# LIN_break2.net
KiCad netlist of a schematic drawn in Altium Designer
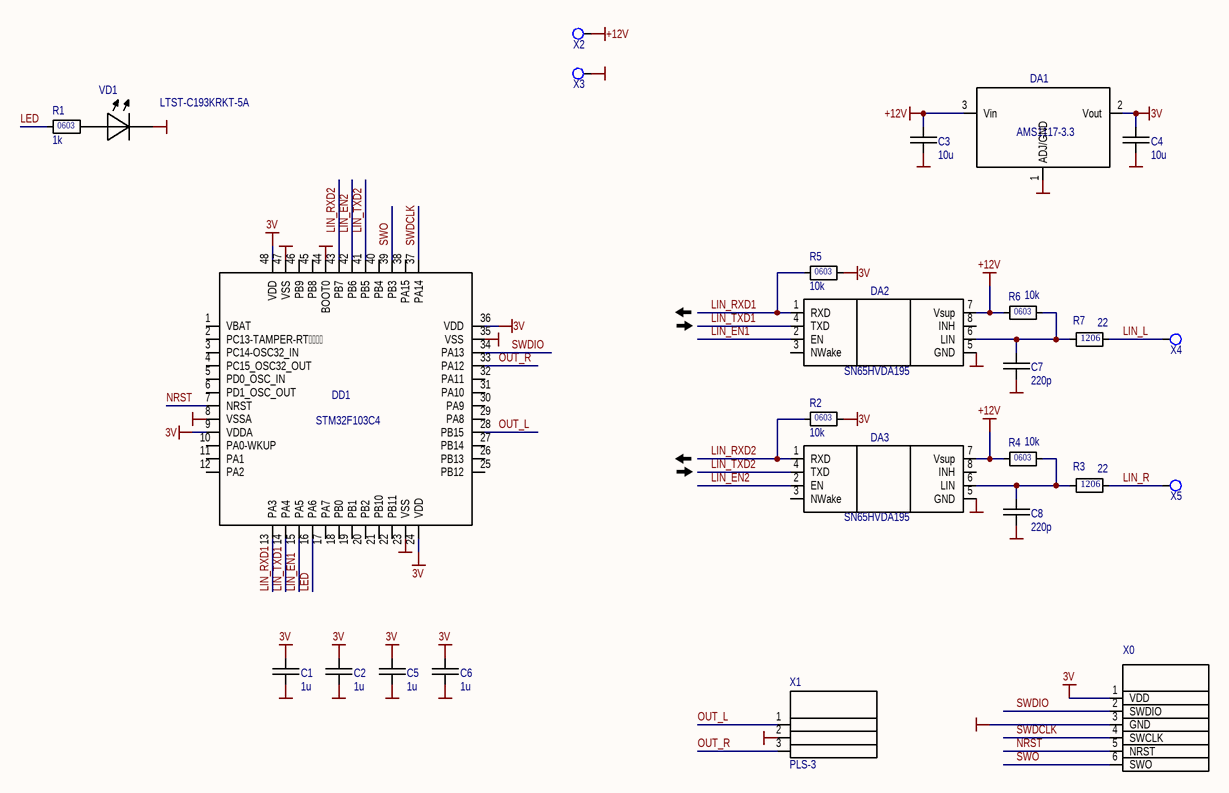
[diagram p0: LIN_break2.SchDoc]

(export (version "E")
  (design (tool "Eeschema 10.0.6"))
  (components
    (comp (ref "C1")
      (value "1u")
      (footprint "C0603")
      (description "General  ceramic capacitor")
      (fields (field (name "PART NUMBER") "GRM185C81A105ME36#") (field (name "VOLTAGE") "10V"))
      (libsource (lib "altium") (part "Capacitor"))
    )
    (comp (ref "C2")
      (value "1u")
      (footprint "C0603")
      (description "General  ceramic capacitor")
      (fields (field (name "PART NUMBER") "GRM185C81A105ME36#") (field (name "VOLTAGE") "10V"))
      (libsource (lib "altium") (part "Capacitor"))
    )
    (comp (ref "C3")
      (value "10u")
      (footprint "C0805")
      (description "General  ceramic capacitor")
      (fields (field (name "PART NUMBER") "GRM21BC81A106KE18#") (field (name "VOLTAGE") "10V"))
      (libsource (lib "altium") (part "Capacitor"))
    )
    (comp (ref "C4")
      (value "10u")
      (footprint "C0805")
      (description "General  ceramic capacitor")
      (fields (field (name "PART NUMBER") "GRM21BC81A106KE18#") (field (name "VOLTAGE") "10V"))
      (libsource (lib "altium") (part "Capacitor"))
    )
    (comp (ref "C5")
      (value "1u")
      (footprint "C0603")
      (description "General  ceramic capacitor")
      (fields (field (name "PART NUMBER") "GRM185C81A105ME36#") (field (name "VOLTAGE") "10V"))
      (libsource (lib "altium") (part "Capacitor"))
    )
    (comp (ref "C6")
      (value "1u")
      (footprint "C0603")
      (description "General  ceramic capacitor")
      (fields (field (name "PART NUMBER") "GRM185C81A105ME36#") (field (name "VOLTAGE") "10V"))
      (libsource (lib "altium") (part "Capacitor"))
    )
    (comp (ref "C7")
      (value "220p")
      (footprint "C0603")
      (description "General  ceramic capacitor")
      (fields (field (name "PART NUMBER") "GRM188R72A221MA01#") (field (name "VOLTAGE") "100V"))
      (libsource (lib "altium") (part "Capacitor"))
    )
    (comp (ref "C8")
      (value "220p")
      (footprint "C0603")
      (description "General  ceramic capacitor")
      (fields (field (name "PART NUMBER") "GRM188R72A221MA01#") (field (name "VOLTAGE") "100V"))
      (libsource (lib "altium") (part "Capacitor"))
    )
    (comp (ref "DA1")
      (value "~")
      (footprint "LIN_break2:AMS1117-3.3")
      (description "LDO ADJ 0.8mA")
      (fields (field (name "LCSC PART #") "C426566") (field (name "PART NUMBER") "AMS1117-3.3"))
      (libsource (lib "LIN_break2") (part "AMS1117-3.3"))
    )
    (comp (ref "DA2")
      (value "SN65HVDA195")
      (footprint "TI-SOIC8 D")
      (description "LIN driver")
      (fields (field (name "PART NUMBER") "SN65HVDA195QDRQ1") (field (name "LCSC PART #") "C140290"))
      (libsource (lib "altium") (part "SN65HVDA195"))
    )
    (comp (ref "DA3")
      (value "SN65HVDA195")
      (footprint "TI-SOIC8 D")
      (description "LIN driver")
      (fields (field (name "PART NUMBER") "SN65HVDA195QDRQ1") (field (name "LCSC PART #") "C140290"))
      (libsource (lib "altium") (part "SN65HVDA195"))
    )
    (comp (ref "DD1")
      (value "STM32F103C4")
      (footprint "ST-LQFP48")
      (description "16K Flash, 48 pins")
      (fields (field (name "COMPONENT NAME") "STM32F103C4"))
      (libsource (lib "altium") (part "STM32F103-LQFP48"))
    )
    (comp (ref "R1")
      (value "1k")
      (footprint "R0603")
      (description "Thick Film Chip Resistor - CR Series")
      (fields (field (name "PART NUMBER") "CR-03FL7----1k") (field (name "TOLERANCE") "±1%"))
      (libsource (lib "altium") (part "Resistor - 0603"))
    )
    (comp (ref "R2")
      (value "10k")
      (footprint "R0603")
      (description "Thick Film Chip Resistor - CR Series")
      (fields (field (name "PART NUMBER") "CR-03FL7----1k") (field (name "TOLERANCE") "±1%"))
      (libsource (lib "altium") (part "Resistor - 0603"))
    )
    (comp (ref "R3")
      (value "22")
      (footprint "R1206")
      (description "1/4W 200V")
      (fields (field (name "PART NUMBER") "CR-06FL5--22R0"))
      (libsource (lib "altium") (part "Resistor - 1206"))
    )
    (comp (ref "R4")
      (value "10k")
      (footprint "R0603")
      (description "Thick Film Chip Resistor - CR Series")
      (fields (field (name "PART NUMBER") "CR-03FL7----1k") (field (name "TOLERANCE") "±1%"))
      (libsource (lib "altium") (part "Resistor - 0603"))
    )
    (comp (ref "R5")
      (value "10k")
      (footprint "R0603")
      (description "Thick Film Chip Resistor - CR Series")
      (fields (field (name "PART NUMBER") "CR-03FL7----1k") (field (name "TOLERANCE") "±1%"))
      (libsource (lib "altium") (part "Resistor - 0603"))
    )
    (comp (ref "R6")
      (value "10k")
      (footprint "R0603")
      (description "Thick Film Chip Resistor - CR Series")
      (fields (field (name "PART NUMBER") "CR-03FL7----1k") (field (name "TOLERANCE") "±1%"))
      (libsource (lib "altium") (part "Resistor - 0603"))
    )
    (comp (ref "R7")
      (value "22")
      (footprint "R1206")
      (description "1/4W 200V")
      (fields (field (name "PART NUMBER") "CR-06FL5--22R0"))
      (libsource (lib "altium") (part "Resistor - 1206"))
    )
    (comp (ref "VD1")
      (value "Red")
      (footprint "LTST-C193 RED")
      (description "TopView Single Color Chip LED")
      (fields (field (name "PART NUMBER") "LTST-C193KRKT-5A") (field (name "LCSC PART #") "C157741"))
      (libsource (lib "altium") (part "LED"))
    )
    (comp (ref "X0")
      (value "STM32_SMT_DEBUG_JLINK")
      (footprint "STM32_DEBUG_6x1_2mm_pitch")
      (description "Trace-Asynchronous_SW")
      (libsource (lib "altium") (part "STM32_SMT_DEBUG_JLINK"))
    )
    (comp (ref "X1") (value "PLS-3") (footprint "PLS-3") (libsource (lib "altium") (part "Connector-3")))
    (comp (ref "X2")
      (value "1-pin_round NB")
      (footprint "Hole-1-1.6")
      (libsource (lib "altium") (part "1-pin_round NB"))
    )
    (comp (ref "X3")
      (value "1-pin_round NB")
      (footprint "Hole-1-1.6")
      (libsource (lib "altium") (part "1-pin_round NB"))
    )
    (comp (ref "X4")
      (value "1-pin_round NB")
      (footprint "Hole-1-1.6")
      (libsource (lib "altium") (part "1-pin_round NB"))
    )
    (comp (ref "X5")
      (value "1-pin_round NB")
      (footprint "Hole-1-1.6")
      (libsource (lib "altium") (part "1-pin_round NB"))
    )
  )
  (nets
    (net (code "1") (name "+12V") (class "Default")
      (node (ref "C3") (pin "1") (pinfunction "1_1") (pintype "passive"))
      (node (ref "DA1") (pin "3") (pinfunction "Vin_3") (pintype "passive"))
      (node (ref "DA2") (pin "7") (pinfunction "Vsup_7") (pintype "passive"))
      (node (ref "DA3") (pin "7") (pinfunction "Vsup_7") (pintype "passive"))
      (node (ref "R4") (pin "1") (pinfunction "1_1") (pintype "passive"))
      (node (ref "R6") (pin "1") (pinfunction "1_1") (pintype "passive"))
      (node (ref "X2") (pin "1") (pintype "passive"))
    )
    (net (code "2") (name "/LED") (class "Default")
      (node (ref "DD1") (pin "16") (pinfunction "PA6_16") (pintype "passive"))
      (node (ref "R1") (pin "1") (pinfunction "1_1") (pintype "passive"))
    )
    (net (code "3") (name "/LIN_EN1") (class "Default")
      (node (ref "DA2") (pin "2") (pinfunction "EN_2") (pintype "passive"))
      (node (ref "DD1") (pin "15") (pinfunction "PA5_15") (pintype "passive"))
    )
    (net (code "4") (name "/LIN_EN2") (class "Default")
      (node (ref "DA3") (pin "2") (pinfunction "EN_2") (pintype "passive"))
      (node (ref "DD1") (pin "42") (pinfunction "PB6_42") (pintype "passive"))
    )
    (net (code "5") (name "/LIN_L") (class "Default")
      (node (ref "R7") (pin "2") (pinfunction "2_2") (pintype "passive"))
      (node (ref "X4") (pin "1") (pintype "passive"))
    )
    (net (code "6") (name "/LIN_R") (class "Default")
      (node (ref "R3") (pin "2") (pinfunction "2_2") (pintype "passive"))
      (node (ref "X5") (pin "1") (pintype "passive"))
    )
    (net (code "7") (name "/LIN_RXD1") (class "Default")
      (node (ref "DA2") (pin "1") (pinfunction "RXD_1") (pintype "passive"))
      (node (ref "DD1") (pin "13") (pinfunction "PA3_13") (pintype "passive"))
      (node (ref "R5") (pin "1") (pinfunction "1_1") (pintype "passive"))
    )
    (net (code "8") (name "/LIN_RXD2") (class "Default")
      (node (ref "DA3") (pin "1") (pinfunction "RXD_1") (pintype "passive"))
      (node (ref "DD1") (pin "43") (pinfunction "PB7_43") (pintype "passive"))
      (node (ref "R2") (pin "1") (pinfunction "1_1") (pintype "passive"))
    )
    (net (code "9") (name "/LIN_TXD1") (class "Default")
      (node (ref "DA2") (pin "4") (pinfunction "TXD_4") (pintype "passive"))
      (node (ref "DD1") (pin "14") (pinfunction "PA4_14") (pintype "passive"))
    )
    (net (code "10") (name "/LIN_TXD2") (class "Default")
      (node (ref "DA3") (pin "4") (pinfunction "TXD_4") (pintype "passive"))
      (node (ref "DD1") (pin "41") (pinfunction "PB5_41") (pintype "passive"))
    )
    (net (code "11") (name "/NRST") (class "Default")
      (node (ref "DD1") (pin "7") (pinfunction "NRST_7") (pintype "passive"))
      (node (ref "X0") (pin "5") (pinfunction "NRST_5") (pintype "passive"))
    )
    (net (code "12") (name "/OUT_L") (class "Default")
      (node (ref "DD1") (pin "28") (pinfunction "PB15_28") (pintype "passive"))
      (node (ref "X1") (pin "1") (pintype "passive"))
    )
    (net (code "13") (name "/OUT_R") (class "Default")
      (node (ref "DD1") (pin "33") (pinfunction "PA12_33") (pintype "passive"))
      (node (ref "X1") (pin "3") (pintype "passive"))
    )
    (net (code "14") (name "/SWDCLK") (class "Default")
      (node (ref "DD1") (pin "37") (pinfunction "PA14_37") (pintype "passive"))
      (node (ref "X0") (pin "4") (pinfunction "SWCLK_4") (pintype "passive"))
    )
    (net (code "15") (name "/SWDIO") (class "Default")
      (node (ref "DD1") (pin "34") (pinfunction "PA13_34") (pintype "passive"))
      (node (ref "X0") (pin "2") (pinfunction "SWDIO_2") (pintype "passive"))
    )
    (net (code "16") (name "/SWO") (class "Default")
      (node (ref "DD1") (pin "39") (pinfunction "PB3_39") (pintype "passive"))
      (node (ref "X0") (pin "6") (pinfunction "SWO_6") (pintype "passive"))
    )
    (net (code "17") (name "3V") (class "Default")
      (node (ref "C1") (pin "1") (pinfunction "1_1") (pintype "passive"))
      (node (ref "C2") (pin "1") (pinfunction "1_1") (pintype "passive"))
      (node (ref "C4") (pin "1") (pinfunction "1_1") (pintype "passive"))
      (node (ref "C5") (pin "1") (pinfunction "1_1") (pintype "passive"))
      (node (ref "C6") (pin "1") (pinfunction "1_1") (pintype "passive"))
      (node (ref "DA1") (pin "2") (pinfunction "Vout_2") (pintype "passive"))
      (node (ref "DD1") (pin "24") (pinfunction "VDD_24") (pintype "passive"))
      (node (ref "DD1") (pin "36") (pinfunction "VDD_36") (pintype "passive"))
      (node (ref "DD1") (pin "48") (pinfunction "VDD_48") (pintype "passive"))
      (node (ref "DD1") (pin "9") (pinfunction "VDDA_9") (pintype "passive"))
      (node (ref "R2") (pin "2") (pinfunction "2_2") (pintype "passive"))
      (node (ref "R5") (pin "2") (pinfunction "2_2") (pintype "passive"))
      (node (ref "X0") (pin "1") (pinfunction "VDD_1") (pintype "passive"))
    )
    (net (code "18") (name "GND") (class "Default")
      (node (ref "C1") (pin "2") (pinfunction "2_2") (pintype "passive"))
      (node (ref "C2") (pin "2") (pinfunction "2_2") (pintype "passive"))
      (node (ref "C3") (pin "2") (pinfunction "2_2") (pintype "passive"))
      (node (ref "C4") (pin "2") (pinfunction "2_2") (pintype "passive"))
      (node (ref "C5") (pin "2") (pinfunction "2_2") (pintype "passive"))
      (node (ref "C6") (pin "2") (pinfunction "2_2") (pintype "passive"))
      (node (ref "C7") (pin "2") (pinfunction "2_2") (pintype "passive"))
      (node (ref "C8") (pin "2") (pinfunction "2_2") (pintype "passive"))
      (node (ref "DA1") (pin "1") (pinfunction "ADJ/GND_1") (pintype "passive"))
      (node (ref "DA2") (pin "5") (pinfunction "GND_5") (pintype "passive"))
      (node (ref "DA3") (pin "5") (pinfunction "GND_5") (pintype "passive"))
      (node (ref "DD1") (pin "23") (pinfunction "VSS_23") (pintype "passive"))
      (node (ref "DD1") (pin "35") (pinfunction "VSS_35") (pintype "passive"))
      (node (ref "DD1") (pin "44") (pinfunction "BOOT0_44") (pintype "passive"))
      (node (ref "DD1") (pin "47") (pinfunction "VSS_47") (pintype "passive"))
      (node (ref "DD1") (pin "8") (pinfunction "VSSA_8") (pintype "passive"))
      (node (ref "VD1") (pin "1") (pinfunction "C_1") (pintype "passive"))
      (node (ref "X0") (pin "3") (pinfunction "GND_3") (pintype "passive"))
      (node (ref "X1") (pin "2") (pintype "passive"))
      (node (ref "X3") (pin "1") (pintype "passive"))
    )
    (net (code "19") (name "Net-(DA2-LIN)") (class "Default")
      (node (ref "C7") (pin "1") (pinfunction "1_1") (pintype "passive"))
      (node (ref "DA2") (pin "6") (pinfunction "LIN_6") (pintype "passive"))
      (node (ref "R6") (pin "2") (pinfunction "2_2") (pintype "passive"))
      (node (ref "R7") (pin "1") (pinfunction "1_1") (pintype "passive"))
    )
    (net (code "20") (name "Net-(DA3-LIN)") (class "Default")
      (node (ref "C8") (pin "1") (pinfunction "1_1") (pintype "passive"))
      (node (ref "DA3") (pin "6") (pinfunction "LIN_6") (pintype "passive"))
      (node (ref "R3") (pin "1") (pinfunction "1_1") (pintype "passive"))
      (node (ref "R4") (pin "2") (pinfunction "2_2") (pintype "passive"))
    )
    (net (code "21") (name "Net-(VD1-A)") (class "Default")
      (node (ref "R1") (pin "2") (pinfunction "2_2") (pintype "passive"))
      (node (ref "VD1") (pin "2") (pinfunction "A_2") (pintype "passive"))
    )
    (net (code "22") (name "unconnected-(DA2-INH-Pad8)") (class "Default")
      (node (ref "DA2") (pin "8") (pinfunction "INH_8") (pintype "passive"))
    )
    (net (code "23") (name "unconnected-(DA2-NWake-Pad3)") (class "Default")
      (node (ref "DA2") (pin "3") (pinfunction "NWake_3") (pintype "passive"))
    )
    (net (code "24") (name "unconnected-(DA3-INH-Pad8)") (class "Default")
      (node (ref "DA3") (pin "8") (pinfunction "INH_8") (pintype "passive"))
    )
    (net (code "25") (name "unconnected-(DA3-NWake-Pad3)") (class "Default")
      (node (ref "DA3") (pin "3") (pinfunction "NWake_3") (pintype "passive"))
    )
    (net (code "26") (name "unconnected-(DD1-PA0-WKUP-Pad10)") (class "Default")
      (node (ref "DD1") (pin "10") (pinfunction "PA0-WKUP_10") (pintype "passive"))
    )
    (net (code "27") (name "unconnected-(DD1-PA1-Pad11)") (class "Default")
      (node (ref "DD1") (pin "11") (pinfunction "PA1_11") (pintype "passive"))
    )
    (net (code "28") (name "unconnected-(DD1-PA2-Pad12)") (class "Default")
      (node (ref "DD1") (pin "12") (pinfunction "PA2_12") (pintype "passive"))
    )
    (net (code "29") (name "unconnected-(DD1-PA7-Pad17)") (class "Default")
      (node (ref "DD1") (pin "17") (pinfunction "PA7_17") (pintype "passive"))
    )
    (net (code "30") (name "unconnected-(DD1-PA8-Pad29)") (class "Default")
      (node (ref "DD1") (pin "29") (pinfunction "PA8_29") (pintype "passive"))
    )
    (net (code "31") (name "unconnected-(DD1-PA9-Pad30)") (class "Default")
      (node (ref "DD1") (pin "30") (pinfunction "PA9_30") (pintype "passive"))
    )
    (net (code "32") (name "unconnected-(DD1-PA10-Pad31)") (class "Default")
      (node (ref "DD1") (pin "31") (pinfunction "PA10_31") (pintype "passive"))
    )
    (net (code "33") (name "unconnected-(DD1-PA11-Pad32)") (class "Default")
      (node (ref "DD1") (pin "32") (pinfunction "PA11_32") (pintype "passive"))
    )
    (net (code "34") (name "unconnected-(DD1-PA15-Pad38)") (class "Default")
      (node (ref "DD1") (pin "38") (pinfunction "PA15_38") (pintype "passive"))
    )
    (net (code "35") (name "unconnected-(DD1-PB0-Pad18)") (class "Default")
      (node (ref "DD1") (pin "18") (pinfunction "PB0_18") (pintype "passive"))
    )
    (net (code "36") (name "unconnected-(DD1-PB1-Pad19)") (class "Default")
      (node (ref "DD1") (pin "19") (pinfunction "PB1_19") (pintype "passive"))
    )
    (net (code "37") (name "unconnected-(DD1-PB2-Pad20)") (class "Default")
      (node (ref "DD1") (pin "20") (pinfunction "PB2_20") (pintype "passive"))
    )
    (net (code "38") (name "unconnected-(DD1-PB4-Pad40)") (class "Default")
      (node (ref "DD1") (pin "40") (pinfunction "PB4_40") (pintype "passive"))
    )
    (net (code "39") (name "unconnected-(DD1-PB8-Pad45)") (class "Default")
      (node (ref "DD1") (pin "45") (pinfunction "PB8_45") (pintype "passive"))
    )
    (net (code "40") (name "unconnected-(DD1-PB9-Pad46)") (class "Default")
      (node (ref "DD1") (pin "46") (pinfunction "PB9_46") (pintype "passive"))
    )
    (net (code "41") (name "unconnected-(DD1-PB10-Pad21)") (class "Default")
      (node (ref "DD1") (pin "21") (pinfunction "PB10_21") (pintype "passive"))
    )
    (net (code "42") (name "unconnected-(DD1-PB11-Pad22)") (class "Default")
      (node (ref "DD1") (pin "22") (pinfunction "PB11_22") (pintype "passive"))
    )
    (net (code "43") (name "unconnected-(DD1-PB12-Pad25)") (class "Default")
      (node (ref "DD1") (pin "25") (pinfunction "PB12_25") (pintype "passive"))
    )
    (net (code "44") (name "unconnected-(DD1-PB13-Pad26)") (class "Default")
      (node (ref "DD1") (pin "26") (pinfunction "PB13_26") (pintype "passive"))
    )
    (net (code "45") (name "unconnected-(DD1-PB14-Pad27)") (class "Default")
      (node (ref "DD1") (pin "27") (pinfunction "PB14_27") (pintype "passive"))
    )
    (net (code "46") (name "unconnected-(DD1-PC13-TAMPER-RT-Pad2)") (class "Default")
      (node (ref "DD1") (pin "2") (pinfunction "PC13-TAMPER-RT_2") (pintype "passive"))
    )
    (net (code "47") (name "unconnected-(DD1-PC14-OSC32_IN-Pad3)") (class "Default")
      (node (ref "DD1") (pin "3") (pinfunction "PC14-OSC32_IN_3") (pintype "passive"))
    )
    (net (code "48") (name "unconnected-(DD1-PC15_OSC32_OUT-Pad4)") (class "Default")
      (node (ref "DD1") (pin "4") (pinfunction "PC15_OSC32_OUT_4") (pintype "passive"))
    )
    (net (code "49") (name "unconnected-(DD1-PD0_OSC_IN-Pad5)") (class "Default")
      (node (ref "DD1") (pin "5") (pinfunction "PD0_OSC_IN_5") (pintype "passive"))
    )
    (net (code "50") (name "unconnected-(DD1-PD1_OSC_OUT-Pad6)") (class "Default")
      (node (ref "DD1") (pin "6") (pinfunction "PD1_OSC_OUT_6") (pintype "passive"))
    )
    (net (code "51") (name "unconnected-(DD1-VBAT-Pad1)") (class "Default")
      (node (ref "DD1") (pin "1") (pinfunction "VBAT_1") (pintype "passive"))
    )
  )
)
